# Temperature_sensor_iron.net
KiCad netlist of a schematic drawn in Altium Designer
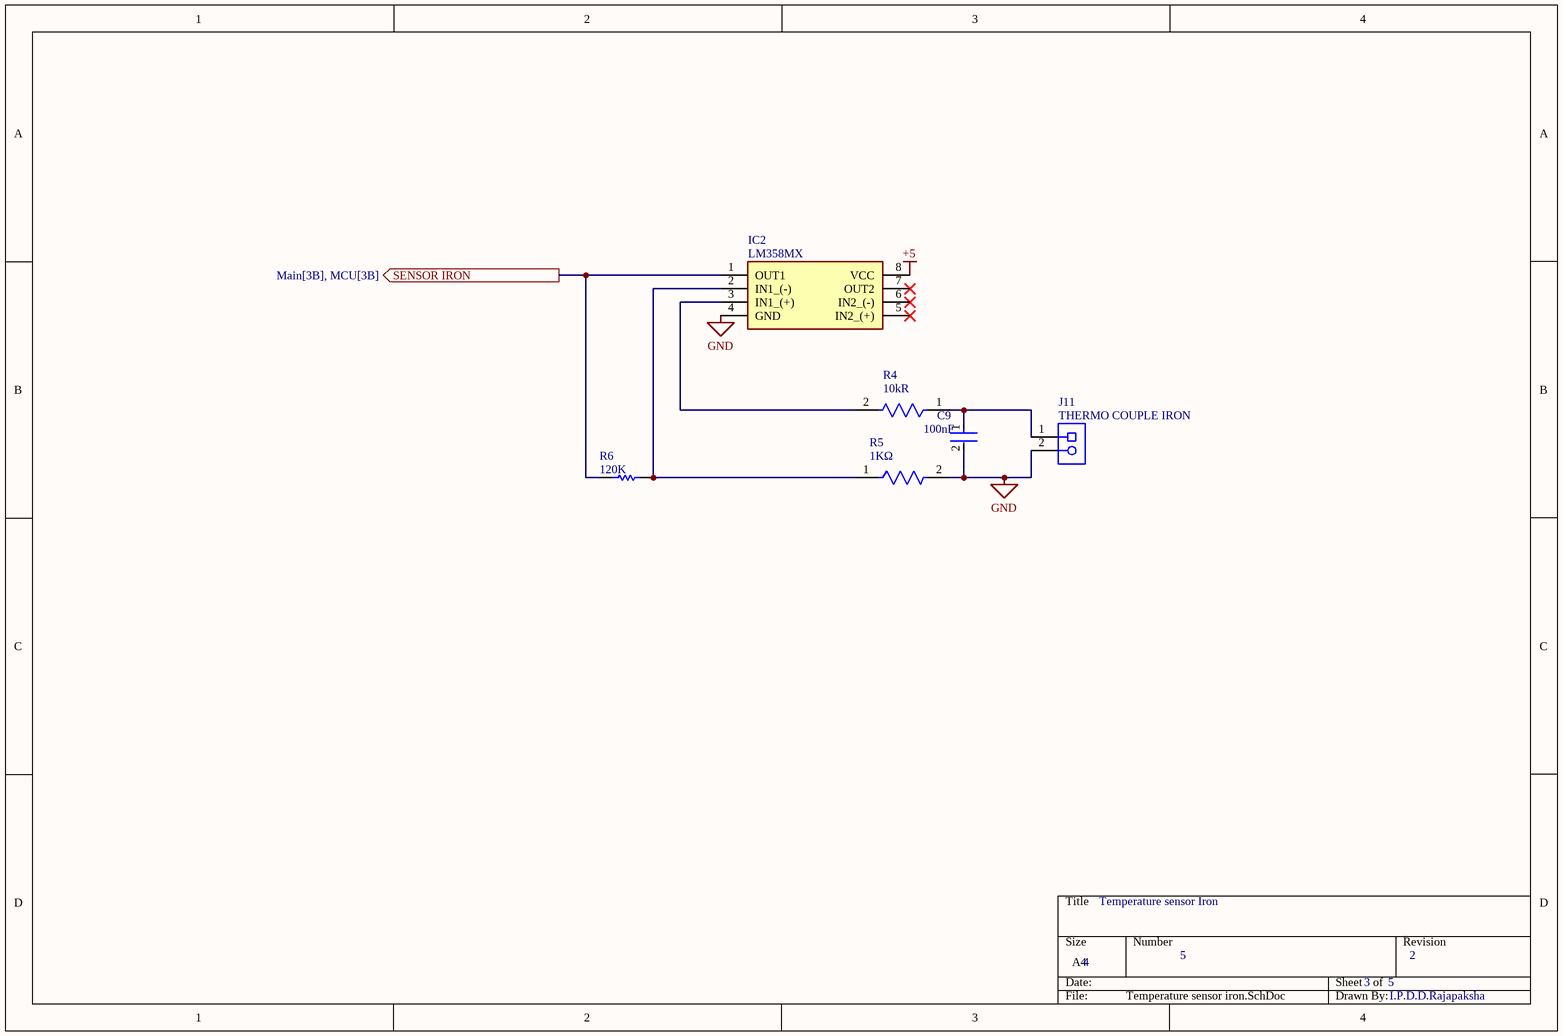
[diagram p0: Temperature sensor iron.SchDoc]

(export (version "E")
  (design (tool "Eeschema 10.0.6"))
  (components
    (comp (ref "C9")
      (value "0805YC104M4T2A")
      (footprint "FP-0805-L_2_01_0_2-W_1_25-IPC_A")
      (description "Automotive Ceramic Capacitor, 0805, 100nF, 20%, X7R, 0.15, 16V")
      (fields (field (name "CAPACITANCE") "100nF") (field (name "TOLERANCE") "20%"))
      (libsource (lib "Altium Content Vault") (part "02cd4be3c70576c341d710602a673aa"))
    )
    (comp (ref "IC2")
      (value "LM358MX")
      (footprint "SamacSys:SOIC127P600X175-8N")
      (description "Integrated Circuit")
      (fields (field (name "MOUSER PART NUMBER") "512-LM358MX"))
      (libsource (lib "*") (part "LM358MX"))
    )
    (comp (ref "J11")
      (value "1729128")
      (footprint "PHOE-1729128-2_V")
      (description "PCB Terminal Block, 13.5 A, 400 V, 2-Pin THD, RoHS, Bulk")
      (fields
        (field (name "MANUFACTURER") "Phoenix Contact")
        (field (name "PARAMETER 1") "THERMO COUPLE IRON")
      )
      (libsource (lib "Altium Content Vault") (part "CN-2P-F-R2"))
    )
    (comp (ref "R4")
      (value "CRCW120610K0FKEA")
      (footprint "FP-CRCW1206-e3-IPC_C")
      (description "RES Thick Film, 10kΩ, 1%, 0.25W, 100ppm/°C, 1206")
      (fields (field (name "TOLERANCE") "1%") (field (name "RESISTANCE") "10kR"))
      (libsource (lib "Altium Content Vault") (part "1029c3af85768c4190bb7ad29bc67b5"))
    )
    (comp (ref "R5")
      (value "1KΩ")
      (footprint "FP-CRGCQ1206-IPC_C")
      (description "CRGCQ1206 1KΩ 0.25W 1% ±100ppm/°C 200V")
      (fields
        (field (name "MANUFACTURER") "TE Connectivity")
        (field (name "MANUFACTURER PART NUMBER") "CRGCQ1206F1K0")
      )
      (libsource (lib "Altium Content Vault") (part "1029c3af85768c4190bb7ad29bc67b5"))
    )
    (comp (ref "R6")
      (value "CRCW1206120KFKEA")
      (footprint "RESC3216X60X45LL10T20")
      (fields (field (name "MANUFACTURER") "Vishay Dale") (field (name "PARAMETER 1") "120K"))
      (libsource (lib "Altium Content Vault") (part "RES"))
    )
  )
  (nets
    (net (code "1") (name "+5") (class "Default")
      (node (ref "IC2") (pin "8") (pinfunction "VCC_8") (pintype "passive"))
    )
    (net (code "2") (name "/SENSOR IRON") (class "Default")
      (node (ref "IC2") (pin "1") (pinfunction "OUT1_1") (pintype "passive"))
      (node (ref "R6") (pin "2") (pinfunction "2_2") (pintype "passive"))
    )
    (net (code "3") (name "GND") (class "Default")
      (node (ref "C9") (pin "2") (pinfunction "2_2") (pintype "passive"))
      (node (ref "IC2") (pin "4") (pinfunction "GND_4") (pintype "passive"))
      (node (ref "J11") (pin "2") (pinfunction "2_2") (pintype "passive"))
      (node (ref "R5") (pin "2") (pinfunction "2_2") (pintype "passive"))
    )
    (net (code "4") (name "Net-(C9-Pad1)") (class "Default")
      (node (ref "C9") (pin "1") (pinfunction "1_1") (pintype "passive"))
      (node (ref "J11") (pin "1") (pinfunction "1_1") (pintype "passive"))
      (node (ref "R4") (pin "1") (pinfunction "1_1") (pintype "passive"))
    )
    (net (code "5") (name "Net-(IC2-IN1_(+))") (class "Default")
      (node (ref "IC2") (pin "3") (pinfunction "IN1_(+)_3") (pintype "passive"))
      (node (ref "R4") (pin "2") (pinfunction "2_2") (pintype "passive"))
    )
    (net (code "6") (name "Net-(IC2-IN1_(-))") (class "Default")
      (node (ref "IC2") (pin "2") (pinfunction "IN1_(-)_2") (pintype "passive"))
      (node (ref "R5") (pin "1") (pinfunction "1_1") (pintype "passive"))
      (node (ref "R6") (pin "1") (pinfunction "1_1") (pintype "passive"))
    )
    (net (code "7") (name "unconnected-(IC2-IN2_(+)-Pad5)") (class "Default")
      (node (ref "IC2") (pin "5") (pinfunction "IN2_(+)_5") (pintype "passive+no_connect"))
    )
    (net (code "8") (name "unconnected-(IC2-IN2_(-)-Pad6)") (class "Default")
      (node (ref "IC2") (pin "6") (pinfunction "IN2_(-)_6") (pintype "passive+no_connect"))
    )
    (net (code "9") (name "unconnected-(IC2-OUT2-Pad7)") (class "Default")
      (node (ref "IC2") (pin "7") (pinfunction "OUT2_7") (pintype "passive+no_connect"))
    )
  )
)
